# ModuleInter.net
KiCad netlist of a schematic drawn in Altium Designer
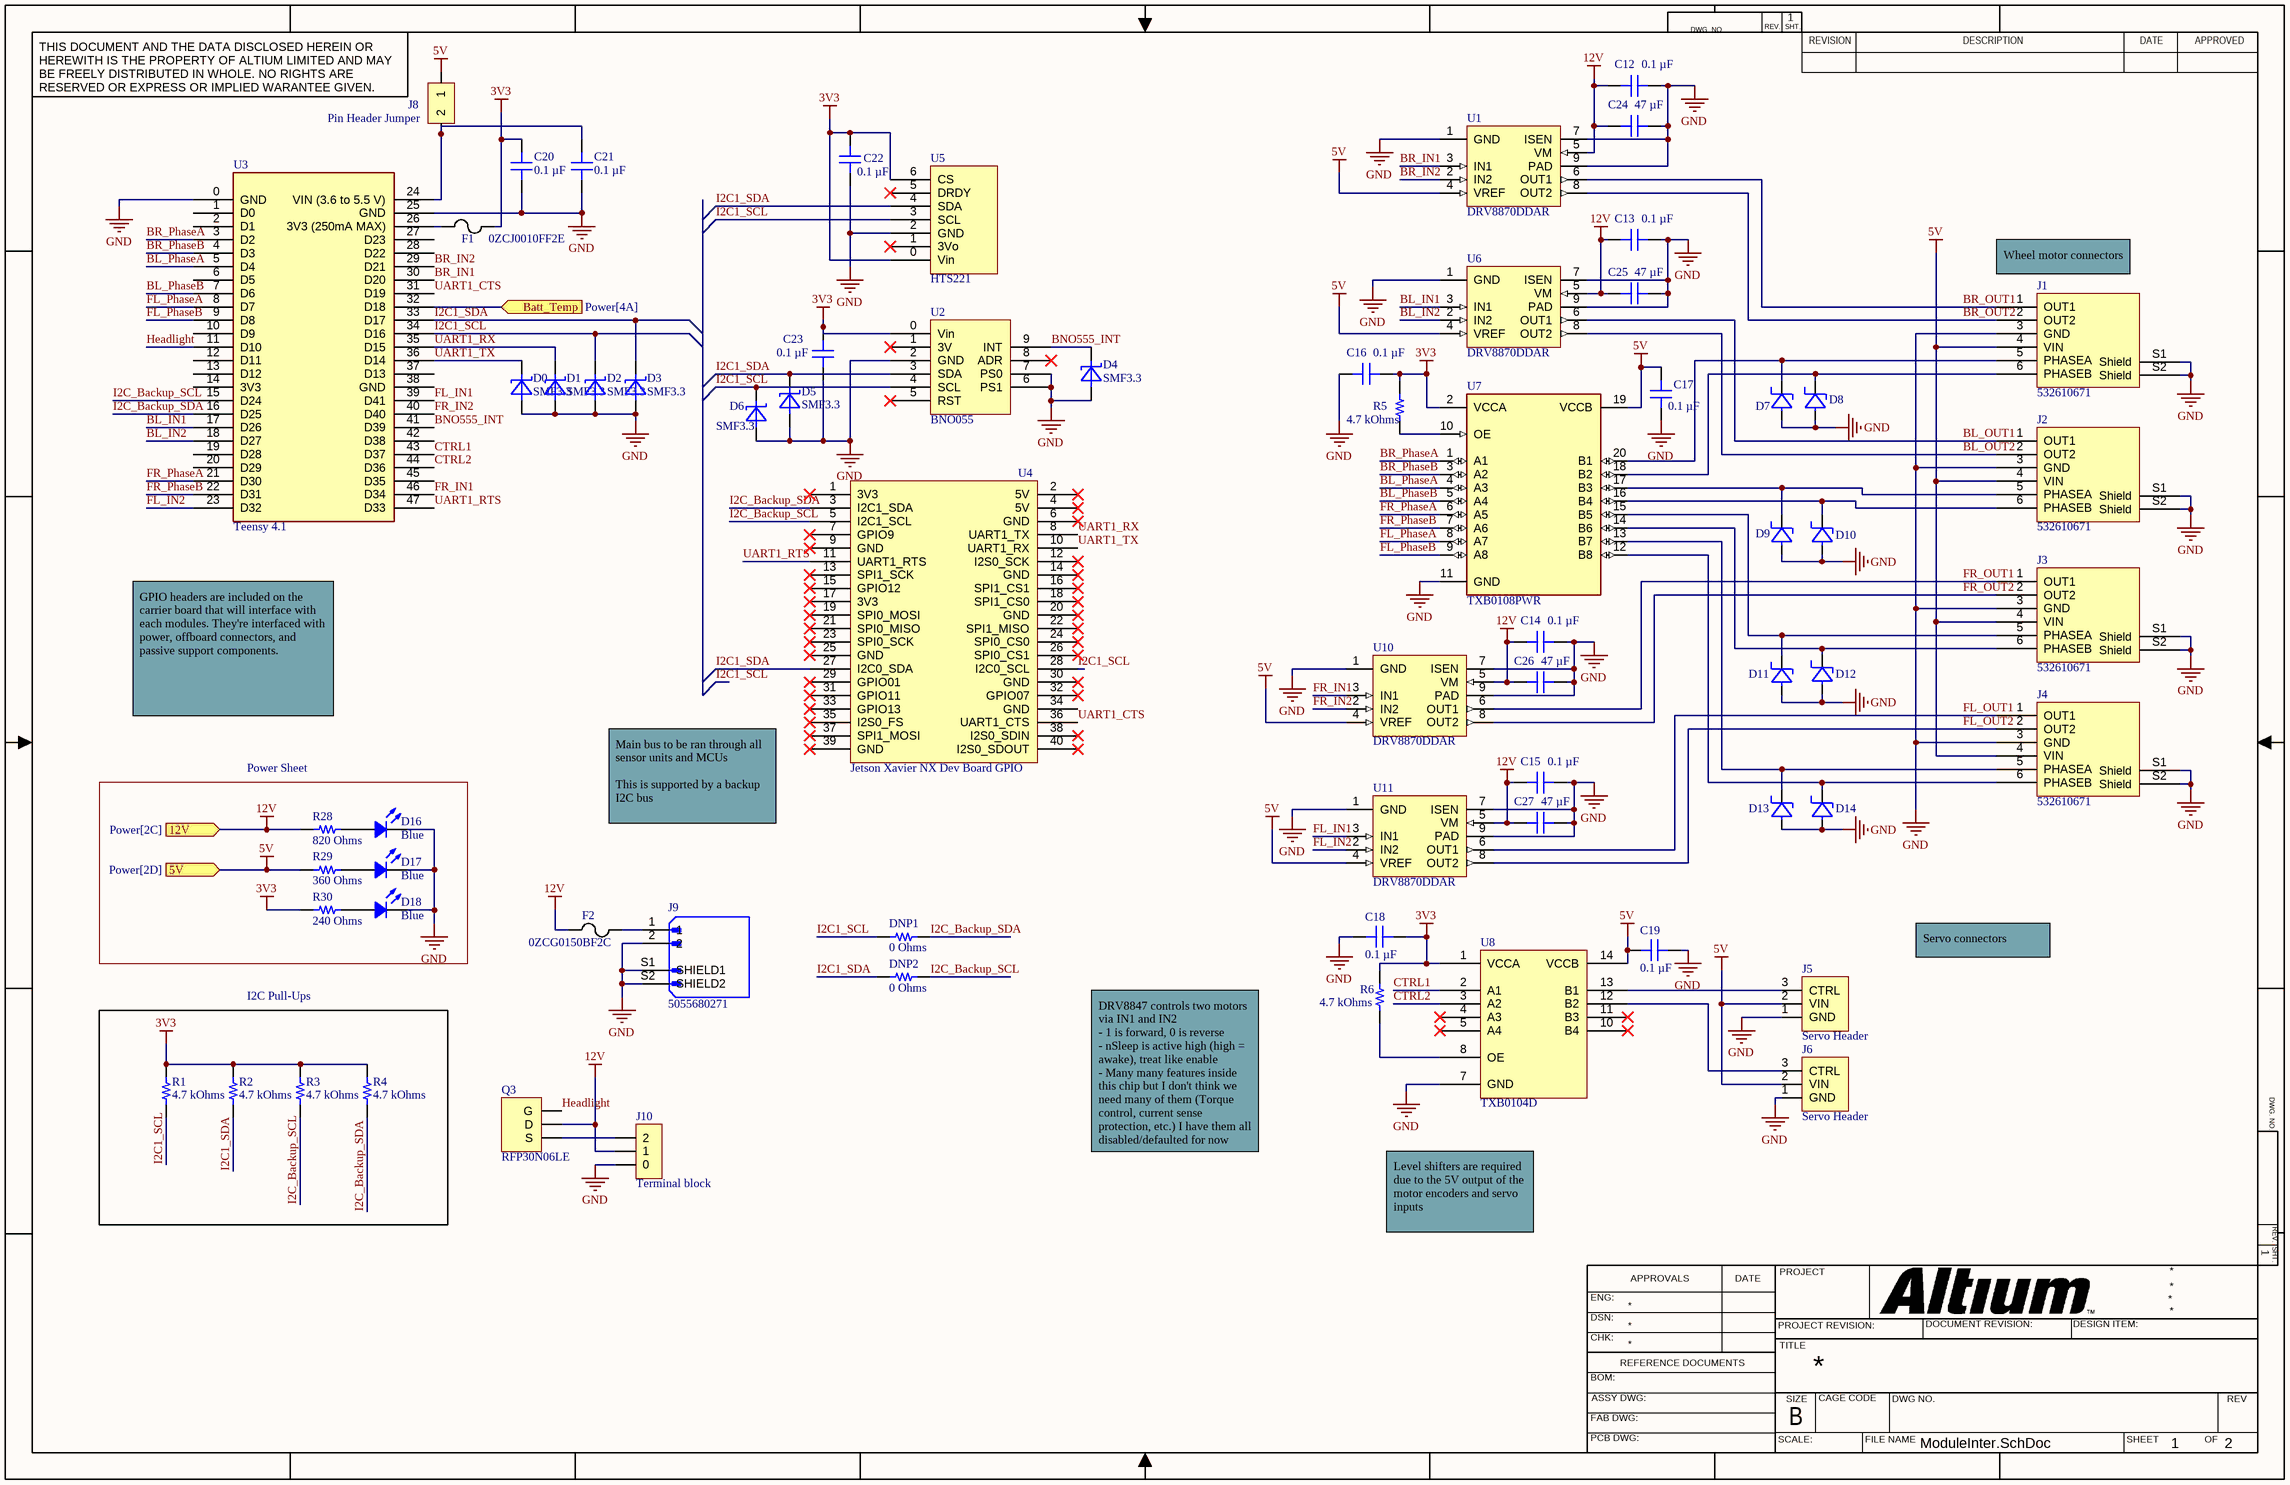
[diagram p0: ModuleInter.SchDoc]

(export (version "E")
  (design (tool "Eeschema 10.0.6"))
  (components
    (comp (ref "C12")
      (value "0.1 µF")
      (footprint "CAP 1206_3216 - 0.8MM")
      (description "CAP CER 0.1UF 50V Y5V 1206")
      (fields (field (name "PART NUMBER") "CC1206MRY5V9BB104") (field (name "MANUFACTURER") "Yageo"))
      (libsource (lib "Celestial Altium Library - altium_library") (part "Capacitor"))
    )
    (comp (ref "C13")
      (value "0.1 µF")
      (footprint "CAP 1206_3216 - 0.8MM")
      (description "CAP CER 0.1UF 50V Y5V 1206")
      (fields (field (name "PART NUMBER") "CC1206MRY5V9BB104") (field (name "MANUFACTURER") "Yageo"))
      (libsource (lib "Celestial Altium Library - altium_library") (part "Capacitor"))
    )
    (comp (ref "C14")
      (value "0.1 µF")
      (footprint "CAP 1206_3216 - 0.8MM")
      (description "CAP CER 0.1UF 50V Y5V 1206")
      (fields (field (name "PART NUMBER") "CC1206MRY5V9BB104") (field (name "MANUFACTURER") "Yageo"))
      (libsource (lib "Celestial Altium Library - altium_library") (part "Capacitor"))
    )
    (comp (ref "C15")
      (value "0.1 µF")
      (footprint "CAP 1206_3216 - 0.8MM")
      (description "CAP CER 0.1UF 50V Y5V 1206")
      (fields (field (name "PART NUMBER") "CC1206MRY5V9BB104") (field (name "MANUFACTURER") "Yageo"))
      (libsource (lib "Celestial Altium Library - altium_library") (part "Capacitor"))
    )
    (comp (ref "C16")
      (value "0.1 µF")
      (footprint "CAP 1206_3216 - 0.8MM")
      (description "CAP CER 0.1UF 50V Y5V 1206")
      (fields (field (name "PART NUMBER") "CC1206MRY5V9BB104") (field (name "MANUFACTURER") "Yageo"))
      (libsource (lib "Celestial Altium Library - altium_library") (part "Capacitor"))
    )
    (comp (ref "C17")
      (value "0.1 µF")
      (footprint "CAP 1206_3216 - 0.8MM")
      (description "CAP CER 0.1UF 50V Y5V 1206")
      (fields (field (name "PART NUMBER") "CC1206MRY5V9BB104") (field (name "MANUFACTURER") "Yageo"))
      (libsource (lib "Celestial Altium Library - altium_library") (part "Capacitor"))
    )
    (comp (ref "C18")
      (value "0.1 µF")
      (footprint "CAP 1206_3216 - 0.8MM")
      (description "CAP CER 0.1UF 50V Y5V 1206")
      (fields (field (name "PART NUMBER") "CC1206MRY5V9BB104") (field (name "MANUFACTURER") "Yageo"))
      (libsource (lib "Celestial Altium Library - altium_library") (part "Capacitor"))
    )
    (comp (ref "C19")
      (value "0.1 µF")
      (footprint "CAP 1206_3216 - 0.8MM")
      (description "CAP CER 0.1UF 50V Y5V 1206")
      (fields (field (name "PART NUMBER") "CC1206MRY5V9BB104") (field (name "MANUFACTURER") "Yageo"))
      (libsource (lib "Celestial Altium Library - altium_library") (part "Capacitor"))
    )
    (comp (ref "C20")
      (value "0.1 µF")
      (footprint "CAP 1206_3216 - 0.8MM")
      (description "CAP CER 0.1UF 50V Y5V 1206")
      (fields (field (name "PART NUMBER") "CC1206MRY5V9BB104") (field (name "MANUFACTURER") "Yageo"))
      (libsource (lib "Celestial Altium Library - altium_library") (part "Capacitor"))
    )
    (comp (ref "C21")
      (value "0.1 µF")
      (footprint "CAP 1206_3216 - 0.8MM")
      (description "CAP CER 0.1UF 50V Y5V 1206")
      (fields (field (name "PART NUMBER") "CC1206MRY5V9BB104") (field (name "MANUFACTURER") "Yageo"))
      (libsource (lib "Celestial Altium Library - altium_library") (part "Capacitor"))
    )
    (comp (ref "C22")
      (value "0.1 µF")
      (footprint "CAP 1206_3216 - 0.8MM")
      (description "CAP CER 0.1UF 50V Y5V 1206")
      (fields (field (name "PART NUMBER") "CC1206MRY5V9BB104") (field (name "MANUFACTURER") "Yageo"))
      (libsource (lib "Celestial Altium Library - altium_library") (part "Capacitor"))
    )
    (comp (ref "C23")
      (value "0.1 µF")
      (footprint "CAP 1206_3216 - 0.8MM")
      (description "CAP CER 0.1UF 50V Y5V 1206")
      (fields (field (name "PART NUMBER") "CC1206MRY5V9BB104") (field (name "MANUFACTURER") "Yageo"))
      (libsource (lib "Celestial Altium Library - altium_library") (part "Capacitor"))
    )
    (comp (ref "C24")
      (value "47 µF")
      (footprint "CAP 1206_3216 - 0.8MM")
      (description "CAP CER 47UF 6.3V X5R 1206")
      (fields (field (name "PART NUMBER") "JMK316ABJ476MD-T") (field (name "MANUFACTURER") "Taiyo Yuden"))
      (libsource (lib "Celestial Altium Library - altium_library") (part "Capacitor"))
    )
    (comp (ref "C25")
      (value "47 µF")
      (footprint "CAP 1206_3216 - 0.8MM")
      (description "CAP CER 47UF 6.3V X5R 1206")
      (fields (field (name "PART NUMBER") "JMK316ABJ476MD-T") (field (name "MANUFACTURER") "Taiyo Yuden"))
      (libsource (lib "Celestial Altium Library - altium_library") (part "Capacitor"))
    )
    (comp (ref "C26")
      (value "47 µF")
      (footprint "CAP 1206_3216 - 0.8MM")
      (description "CAP CER 47UF 6.3V X5R 1206")
      (fields (field (name "PART NUMBER") "JMK316ABJ476MD-T") (field (name "MANUFACTURER") "Taiyo Yuden"))
      (libsource (lib "Celestial Altium Library - altium_library") (part "Capacitor"))
    )
    (comp (ref "C27")
      (value "47 µF")
      (footprint "CAP 1206_3216 - 0.8MM")
      (description "CAP CER 47UF 6.3V X5R 1206")
      (fields (field (name "PART NUMBER") "JMK316ABJ476MD-T") (field (name "MANUFACTURER") "Taiyo Yuden"))
      (libsource (lib "Celestial Altium Library - altium_library") (part "Capacitor"))
    )
    (comp (ref "D0")
      (value "SMF3.3")
      (footprint "SODFL3718X108N")
      (description "6.8V Clamp 30A Ipp Tvs Diode Surface Mount SOD-123FL")
      (fields (field (name "DIGI-KEY_PART_NUMBER") "F7701CT-ND") (field (name "MF") "Littelfuse Inc."))
      (libsource (lib "CBSchLib") (part "SMF3.3"))
    )
    (comp (ref "D1")
      (value "SMF3.3")
      (footprint "SODFL3718X108N")
      (description "6.8V Clamp 30A Ipp Tvs Diode Surface Mount SOD-123FL")
      (fields (field (name "DIGI-KEY_PART_NUMBER") "F7701CT-ND") (field (name "MF") "Littelfuse Inc."))
      (libsource (lib "CBSchLib") (part "SMF3.3"))
    )
    (comp (ref "D2")
      (value "SMF3.3")
      (footprint "SODFL3718X108N")
      (description "6.8V Clamp 30A Ipp Tvs Diode Surface Mount SOD-123FL")
      (fields (field (name "DIGI-KEY_PART_NUMBER") "F7701CT-ND") (field (name "MF") "Littelfuse Inc."))
      (libsource (lib "CBSchLib") (part "SMF3.3"))
    )
    (comp (ref "D3")
      (value "SMF3.3")
      (footprint "SODFL3718X108N")
      (description "6.8V Clamp 30A Ipp Tvs Diode Surface Mount SOD-123FL")
      (fields (field (name "DIGI-KEY_PART_NUMBER") "F7701CT-ND") (field (name "MF") "Littelfuse Inc."))
      (libsource (lib "CBSchLib") (part "SMF3.3"))
    )
    (comp (ref "D4")
      (value "SMF3.3")
      (footprint "SODFL3718X108N")
      (description "6.8V Clamp 30A Ipp Tvs Diode Surface Mount SOD-123FL")
      (fields (field (name "DIGI-KEY_PART_NUMBER") "F7701CT-ND") (field (name "MF") "Littelfuse Inc."))
      (libsource (lib "CBSchLib") (part "SMF3.3"))
    )
    (comp (ref "D5")
      (value "SMF3.3")
      (footprint "SODFL3718X108N")
      (description "6.8V Clamp 30A Ipp Tvs Diode Surface Mount SOD-123FL")
      (fields (field (name "DIGI-KEY_PART_NUMBER") "F7701CT-ND") (field (name "MF") "Littelfuse Inc."))
      (libsource (lib "CBSchLib") (part "SMF3.3"))
    )
    (comp (ref "D6")
      (value "SMF3.3")
      (footprint "SODFL3718X108N")
      (description "6.8V Clamp 30A Ipp Tvs Diode Surface Mount SOD-123FL")
      (fields (field (name "DIGI-KEY_PART_NUMBER") "F7701CT-ND") (field (name "MF") "Littelfuse Inc."))
      (libsource (lib "CBSchLib") (part "SMF3.3"))
    )
    (comp (ref "D7")
      (value "SMBJ5.0CA-13-F")
      (footprint "SMB_DIO")
      (description "DIODE ZENER 6.2V 600W")
      (libsource (lib "CBSchLib") (part "SMBJ5.0CA-13-F"))
    )
    (comp (ref "D8")
      (value "SMBJ5.0CA-13-F")
      (footprint "SMB_DIO")
      (description "DIODE ZENER 6.2V 600W")
      (libsource (lib "CBSchLib") (part "SMBJ5.0CA-13-F"))
    )
    (comp (ref "D9")
      (value "SMBJ5.0CA-13-F")
      (footprint "SMB_DIO")
      (description "DIODE ZENER 6.2V 600W")
      (libsource (lib "CBSchLib") (part "SMBJ5.0CA-13-F"))
    )
    (comp (ref "D10")
      (value "SMBJ5.0CA-13-F")
      (footprint "SMB_DIO")
      (description "DIODE ZENER 6.2V 600W")
      (libsource (lib "CBSchLib") (part "SMBJ5.0CA-13-F"))
    )
    (comp (ref "D11")
      (value "SMBJ5.0CA-13-F")
      (footprint "SMB_DIO")
      (description "DIODE ZENER 6.2V 600W")
      (libsource (lib "CBSchLib") (part "SMBJ5.0CA-13-F"))
    )
    (comp (ref "D12")
      (value "SMBJ5.0CA-13-F")
      (footprint "SMB_DIO")
      (description "DIODE ZENER 6.2V 600W")
      (libsource (lib "CBSchLib") (part "SMBJ5.0CA-13-F"))
    )
    (comp (ref "D13")
      (value "SMBJ5.0CA-13-F")
      (footprint "SMB_DIO")
      (description "DIODE ZENER 6.2V 600W")
      (libsource (lib "CBSchLib") (part "SMBJ5.0CA-13-F"))
    )
    (comp (ref "D14")
      (value "SMBJ5.0CA-13-F")
      (footprint "SMB_DIO")
      (description "DIODE ZENER 6.2V 600W")
      (libsource (lib "CBSchLib") (part "SMBJ5.0CA-13-F"))
    )
    (comp (ref "D16")
      (value "Blue")
      (footprint "LED 1206_3216 BLUE")
      (description "LED BLUE CLEAR 1206 SMD")
      (fields (field (name "PART NUMBER") "LTST-C150TBKT") (field (name "MANUFACTURER") "Lite-On Inc."))
      (libsource (lib "Celestial Altium Library - altium_library") (part "LED"))
    )
    (comp (ref "D17")
      (value "Blue")
      (footprint "LED 1206_3216 BLUE")
      (description "LED BLUE CLEAR 1206 SMD")
      (fields (field (name "PART NUMBER") "LTST-C150TBKT") (field (name "MANUFACTURER") "Lite-On Inc."))
      (libsource (lib "Celestial Altium Library - altium_library") (part "LED"))
    )
    (comp (ref "D18")
      (value "Blue")
      (footprint "LED 1206_3216 BLUE")
      (description "LED BLUE CLEAR 1206 SMD")
      (fields (field (name "PART NUMBER") "LTST-C150TBKT") (field (name "MANUFACTURER") "Lite-On Inc."))
      (libsource (lib "Celestial Altium Library - altium_library") (part "LED"))
    )
    (comp (ref "DNP1")
      (value "0 Ohms")
      (footprint "RES 1206_3216")
      (description "RES 0 OHM JUMPER 1/2W 1206")
      (fields (field (name "PART NUMBER") "RC1206JR-7W0RL") (field (name "MANUFACTURER") "Yageo"))
      (libsource (lib "Celestial Altium Library - altium_library") (part "Resistor"))
    )
    (comp (ref "DNP2")
      (value "0 Ohms")
      (footprint "RES 1206_3216")
      (description "RES 0 OHM JUMPER 1/2W 1206")
      (fields (field (name "PART NUMBER") "RC1206JR-7W0RL") (field (name "MANUFACTURER") "Yageo"))
      (libsource (lib "Celestial Altium Library - altium_library") (part "Resistor"))
    )
    (comp (ref "F1")
      (value "0ZCJ0010FF2E")
      (footprint "RESC3216X125N")
      (description "Polymeric PTC Resettable Fuse 60V 100 mA Ih Surface Mount 1206 (3216 Metric), Concave")
      (fields (field (name "MF") "Bel Fuse"))
      (libsource (lib "CBSchLib") (part "0ZCJ0010FF2E"))
    )
    (comp (ref "F2")
      (value "0ZCG0150BF2C")
      (footprint "0ZCG_BEL")
      (description "Polymeric PTC Resettable Fuse 24V 1.5 A Ih Surface Mount 1812 (4532 Metric), Concave")
      (fields (field (name "COPYRIGHT") "Copyright (C) 2023 Ultra Librarian. All rights reserved."))
      (libsource (lib "CBSchLib") (part "0ZCG0150BF2C"))
    )
    (comp (ref "J1")
      (value "532610671")
      (footprint "MOLEX_532610671")
      (description "Conn Shrouded Header (4 Sides) HDR 6 POS 1.25mm Solder RA Side Entry SMD PicoBlade™ T/R")
      (libsource (lib "CBSchLib") (part "532610671"))
    )
    (comp (ref "J2")
      (value "532610671")
      (footprint "MOLEX_532610671")
      (description "Conn Shrouded Header (4 Sides) HDR 6 POS 1.25mm Solder RA Side Entry SMD PicoBlade™ T/R")
      (libsource (lib "CBSchLib") (part "532610671"))
    )
    (comp (ref "J3")
      (value "532610671")
      (footprint "MOLEX_532610671")
      (description "Conn Shrouded Header (4 Sides) HDR 6 POS 1.25mm Solder RA Side Entry SMD PicoBlade™ T/R")
      (libsource (lib "CBSchLib") (part "532610671"))
    )
    (comp (ref "J4")
      (value "532610671")
      (footprint "MOLEX_532610671")
      (description "Conn Shrouded Header (4 Sides) HDR 6 POS 1.25mm Solder RA Side Entry SMD PicoBlade™ T/R")
      (libsource (lib "CBSchLib") (part "532610671"))
    )
    (comp (ref "J5")
      (value "Servo Header")
      (footprint "Servo Header")
      (description "3P jumper header")
      (libsource (lib "CBSchLib") (part "Servo Header"))
    )
    (comp (ref "J6")
      (value "Servo Header")
      (footprint "Servo Header")
      (description "3P jumper header")
      (libsource (lib "CBSchLib") (part "Servo Header"))
    )
    (comp (ref "J8")
      (value "Pin Header Jumper")
      (footprint "Pin Header Jumper")
      (libsource (lib "CBSchLib") (part "Pin Header Jumper"))
    )
    (comp (ref "J9")
      (value "5055680271")
      (footprint "MOLEX_5055680271")
      (fields (field (name "MF") "Molex"))
      (libsource (lib "CBSchLib") (part "5055680271"))
    )
    (comp (ref "J10")
      (value "Terminal block")
      (footprint "Terminal Holes")
      (libsource (lib "CBSchLib") (part "Terminal block"))
    )
    (comp (ref "Q3")
      (value "RFP30N06LE")
      (footprint "PWM Fet")
      (description "Standin fro PWM mosfet for Light bar")
      (libsource (lib "CBSchLib") (part "RFP30N06LE"))
    )
    (comp (ref "R1")
      (value "4.7 kOhms")
      (footprint "RES 1206_3216")
      (description "RES SMD 4.7K OHM 1% 1/4W 1206")
      (fields
        (field (name "PART NUMBER") "CRG1206F4K7")
        (field (name "MANUFACTURER") "TE Connectivity Passive Product")
      )
      (libsource (lib "Celestial Altium Library - altium_library") (part "Resistor"))
    )
    (comp (ref "R2")
      (value "4.7 kOhms")
      (footprint "RES 1206_3216")
      (description "RES SMD 4.7K OHM 1% 1/4W 1206")
      (fields
        (field (name "PART NUMBER") "CRG1206F4K7")
        (field (name "MANUFACTURER") "TE Connectivity Passive Product")
      )
      (libsource (lib "Celestial Altium Library - altium_library") (part "Resistor"))
    )
    (comp (ref "R3")
      (value "4.7 kOhms")
      (footprint "RES 1206_3216")
      (description "RES SMD 4.7K OHM 1% 1/4W 1206")
      (fields
        (field (name "PART NUMBER") "CRG1206F4K7")
        (field (name "MANUFACTURER") "TE Connectivity Passive Product")
      )
      (libsource (lib "Celestial Altium Library - altium_library") (part "Resistor"))
    )
    (comp (ref "R4")
      (value "4.7 kOhms")
      (footprint "RES 1206_3216")
      (description "RES SMD 4.7K OHM 1% 1/4W 1206")
      (fields
        (field (name "PART NUMBER") "CRG1206F4K7")
        (field (name "MANUFACTURER") "TE Connectivity Passive Product")
      )
      (libsource (lib "Celestial Altium Library - altium_library") (part "Resistor"))
    )
    (comp (ref "R5")
      (value "4.7 kOhms")
      (footprint "RES 1206_3216")
      (description "RES SMD 4.7K OHM 1% 1/4W 1206")
      (fields
        (field (name "PART NUMBER") "CRG1206F4K7")
        (field (name "MANUFACTURER") "TE Connectivity Passive Product")
      )
      (libsource (lib "Celestial Altium Library - altium_library") (part "Resistor"))
    )
    (comp (ref "R6")
      (value "4.7 kOhms")
      (footprint "RES 1206_3216")
      (description "RES SMD 4.7K OHM 1% 1/4W 1206")
      (fields
        (field (name "PART NUMBER") "CRG1206F4K7")
        (field (name "MANUFACTURER") "TE Connectivity Passive Product")
      )
      (libsource (lib "Celestial Altium Library - altium_library") (part "Resistor"))
    )
    (comp (ref "R28")
      (value "820 Ohms")
      (footprint "RES 1206_3216")
      (description "RES 820 OHM 1% 1/4W 1206")
      (fields
        (field (name "PART NUMBER") "CRGCQ1206F820R")
        (field (name "MANUFACTURER") "TE Connectivity Passive Product")
      )
      (libsource (lib "Celestial Altium Library - altium_library") (part "Resistor"))
    )
    (comp (ref "R29")
      (value "360 Ohms")
      (footprint "RES 1206_3216")
      (description "RES 360 OHM 1% 1/4W 1206")
      (fields
        (field (name "PART NUMBER") "RMCF1206FT360R")
        (field (name "MANUFACTURER") "Stackpole Electronics Inc")
      )
      (libsource (lib "Celestial Altium Library - altium_library") (part "Resistor"))
    )
    (comp (ref "R30")
      (value "240 Ohms")
      (footprint "RES 1206_3216")
      (description "RCS1206 100 240R 1% ET1 E3")
      (fields (field (name "PART NUMBER") "RCS1206240RFKEA") (field (name "MANUFACTURER") "Vishay Dale"))
      (libsource (lib "Celestial Altium Library - altium_library") (part "Resistor"))
    )
    (comp (ref "U1")
      (value "DRV8870DDAR")
      (footprint "VREG_LM5017MR/NOPB")
      (description "45-V, 3.6-A H-bridge motor driver with current regulation 8-SO PowerPAD -40 to 125")
      (fields (field (name "DIGI-KEY_PART_NUMBER") "296-42660-1-ND") (field (name "MF") "Texas Instruments"))
      (libsource (lib "CBSchLib") (part "DRV8870DDAR"))
    )
    (comp (ref "U2")
      (value "BNO055")
      (footprint "BNO555 - Header Mode")
      (libsource (lib "CBSchLib") (part "BNO055"))
    )
    (comp (ref "U3")
      (value "Teensy 4.1")
      (footprint "Teensy 4.1")
      (libsource (lib "CBSchLib") (part "Teensy 4.1"))
    )
    (comp (ref "U4")
      (value "Jetson Xavier NX Dev Board GPIO")
      (footprint "Xavier Interface")
      (libsource (lib "CBSchLib") (part "Jetson Xavier NX Dev Board GPIO"))
    )
    (comp (ref "U5") (value "HTS221") (footprint "HTS221") (libsource (lib "CBSchLib") (part "HTS221")))
    (comp (ref "U6")
      (value "DRV8870DDAR")
      (footprint "VREG_LM5017MR/NOPB")
      (description "45-V, 3.6-A H-bridge motor driver with current regulation 8-SO PowerPAD -40 to 125")
      (fields (field (name "DIGI-KEY_PART_NUMBER") "296-42660-1-ND") (field (name "MF") "Texas Instruments"))
      (libsource (lib "CBSchLib") (part "DRV8870DDAR"))
    )
    (comp (ref "U7")
      (value "TXB0108PWR")
      (footprint "SOP65P640X120-20N")
      (description "8-Bit Bidirectional Voltage-Level Shifter with Auto Direction Sensing and +/-15-kV ESD Protect")
      (fields (field (name "MF") "Texas Instruments") (field (name "DIGI-KEY_PART_NUMBER") "296-21527-2-ND"))
      (libsource (lib "CBSchLib") (part "TXB0108PWR"))
    )
    (comp (ref "U8")
      (value "TXB0104D")
      (footprint "TI SOIC-14 D")
      (description "IC TRNSLTR BIDIRECTIONAL 14SOIC")
      (fields (field (name "MANUFACTURER") "Texas Instruments"))
      (libsource (lib "Celestial Altium Library - altium_library") (part "TI TXB0104"))
    )
    (comp (ref "U10")
      (value "DRV8870DDAR")
      (footprint "VREG_LM5017MR/NOPB")
      (description "45-V, 3.6-A H-bridge motor driver with current regulation 8-SO PowerPAD -40 to 125")
      (fields (field (name "DIGI-KEY_PART_NUMBER") "296-42660-1-ND") (field (name "MF") "Texas Instruments"))
      (libsource (lib "CBSchLib") (part "DRV8870DDAR"))
    )
    (comp (ref "U11")
      (value "DRV8870DDAR")
      (footprint "VREG_LM5017MR/NOPB")
      (description "45-V, 3.6-A H-bridge motor driver with current regulation 8-SO PowerPAD -40 to 125")
      (fields (field (name "DIGI-KEY_PART_NUMBER") "296-42660-1-ND") (field (name "MF") "Texas Instruments"))
      (libsource (lib "CBSchLib") (part "DRV8870DDAR"))
    )
  )
  (nets
    (net (code "1") (name "/BL_IN1") (class "Default")
      (node (ref "U3") (pin "17") (pinfunction "D26_17") (pintype "passive"))
      (node (ref "U6") (pin "3") (pinfunction "IN1_3") (pintype "input"))
    )
    (net (code "2") (name "/BL_IN2") (class "Default")
      (node (ref "U3") (pin "18") (pinfunction "D27_18") (pintype "passive"))
      (node (ref "U6") (pin "2") (pinfunction "IN2_2") (pintype "input"))
    )
    (net (code "3") (name "/BL_OUT1") (class "Default")
      (node (ref "J2") (pin "1") (pinfunction "OUT1_1") (pintype "passive"))
      (node (ref "U6") (pin "6") (pinfunction "OUT1_6") (pintype "output"))
    )
    (net (code "4") (name "/BL_OUT2") (class "Default")
      (node (ref "J2") (pin "2") (pinfunction "OUT2_2") (pintype "passive"))
      (node (ref "U6") (pin "8") (pinfunction "OUT2_8") (pintype "output"))
    )
    (net (code "5") (name "/BL_PhaseA") (class "Default")
      (node (ref "U3") (pin "5") (pinfunction "D4_5") (pintype "passive"))
      (node (ref "U7") (pin "4") (pinfunction "A3_4") (pintype "bidirectional"))
    )
    (net (code "6") (name "/BL_PhaseB") (class "Default")
      (node (ref "U3") (pin "7") (pinfunction "D6_7") (pintype "passive"))
      (node (ref "U7") (pin "5") (pinfunction "A4_5") (pintype "bidirectional"))
    )
    (net (code "7") (name "/BNO555_INT") (class "Default")
      (node (ref "D4") (pin "A") (pinfunction "C_A") (pintype "passive"))
      (node (ref "U2") (pin "9") (pinfunction "INT_9") (pintype "passive"))
      (node (ref "U3") (pin "41") (pinfunction "D39_41") (pintype "passive"))
    )
    (net (code "8") (name "/BR_IN1") (class "Default")
      (node (ref "U1") (pin "3") (pinfunction "IN1_3") (pintype "input"))
      (node (ref "U3") (pin "30") (pinfunction "D20_30") (pintype "passive"))
    )
    (net (code "9") (name "/BR_IN2") (class "Default")
      (node (ref "U1") (pin "2") (pinfunction "IN2_2") (pintype "input"))
      (node (ref "U3") (pin "29") (pinfunction "D21_29") (pintype "passive"))
    )
    (net (code "10") (name "/BR_OUT1") (class "Default")
      (node (ref "J1") (pin "1") (pinfunction "OUT1_1") (pintype "passive"))
      (node (ref "U1") (pin "6") (pinfunction "OUT1_6") (pintype "output"))
    )
    (net (code "11") (name "/BR_OUT2") (class "Default")
      (node (ref "J1") (pin "2") (pinfunction "OUT2_2") (pintype "passive"))
      (node (ref "U1") (pin "8") (pinfunction "OUT2_8") (pintype "output"))
    )
    (net (code "12") (name "/BR_PhaseA") (class "Default")
      (node (ref "U3") (pin "3") (pinfunction "D2_3") (pintype "passive"))
      (node (ref "U7") (pin "1") (pinfunction "A1_1") (pintype "bidirectional"))
    )
    (net (code "13") (name "/BR_PhaseB") (class "Default")
      (node (ref "U3") (pin "4") (pinfunction "D3_4") (pintype "passive"))
      (node (ref "U7") (pin "3") (pinfunction "A2_3") (pintype "bidirectional"))
    )
    (net (code "14") (name "/Batt_Temp") (class "Default")
      (node (ref "U3") (pin "32") (pinfunction "D18_32") (pintype "passive"))
    )
    (net (code "15") (name "/CTRL1") (class "Default")
      (node (ref "U3") (pin "43") (pinfunction "D37_43") (pintype "passive"))
      (node (ref "U8") (pin "2") (pinfunction "A1_2") (pintype "passive"))
    )
    (net (code "16") (name "/CTRL2") (class "Default")
      (node (ref "U3") (pin "44") (pinfunction "D36_44") (pintype "passive"))
      (node (ref "U8") (pin "3") (pinfunction "A2_3") (pintype "passive"))
    )
    (net (code "17") (name "/FL_IN1") (class "Default")
      (node (ref "U11") (pin "3") (pinfunction "IN1_3") (pintype "input"))
      (node (ref "U3") (pin "39") (pinfunction "D41_39") (pintype "passive"))
    )
    (net (code "18") (name "/FL_IN2") (class "Default")
      (node (ref "U11") (pin "2") (pinfunction "IN2_2") (pintype "input"))
      (node (ref "U3") (pin "23") (pinfunction "D32_23") (pintype "passive"))
    )
    (net (code "19") (name "/FL_OUT1") (class "Default")
      (node (ref "J4") (pin "1") (pinfunction "OUT1_1") (pintype "passive"))
      (node (ref "U11") (pin "6") (pinfunction "OUT1_6") (pintype "output"))
    )
    (net (code "20") (name "/FL_OUT2") (class "Default")
      (node (ref "J4") (pin "2") (pinfunction "OUT2_2") (pintype "passive"))
      (node (ref "U11") (pin "8") (pinfunction "OUT2_8") (pintype "output"))
    )
    (net (code "21") (name "/FL_PhaseA") (class "Default")
      (node (ref "U3") (pin "8") (pinfunction "D7_8") (pintype "passive"))
      (node (ref "U7") (pin "8") (pinfunction "A7_8") (pintype "bidirectional"))
    )
    (net (code "22") (name "/FL_PhaseB") (class "Default")
      (node (ref "U3") (pin "9") (pinfunction "D8_9") (pintype "passive"))
      (node (ref "U7") (pin "9") (pinfunction "A8_9") (pintype "bidirectional"))
    )
    (net (code "23") (name "/FR_IN1") (class "Default")
      (node (ref "U10") (pin "3") (pinfunction "IN1_3") (pintype "input"))
      (node (ref "U3") (pin "46") (pinfunction "D34_46") (pintype "passive"))
    )
    (net (code "24") (name "/FR_IN2") (class "Default")
      (node (ref "U10") (pin "2") (pinfunction "IN2_2") (pintype "input"))
      (node (ref "U3") (pin "40") (pinfunction "D40_40") (pintype "passive"))
    )
    (net (code "25") (name "/FR_OUT1") (class "Default")
      (node (ref "J3") (pin "1") (pinfunction "OUT1_1") (pintype "passive"))
      (node (ref "U10") (pin "6") (pinfunction "OUT1_6") (pintype "output"))
    )
    (net (code "26") (name "/FR_OUT2") (class "Default")
      (node (ref "J3") (pin "2") (pinfunction "OUT2_2") (pintype "passive"))
      (node (ref "U10") (pin "8") (pinfunction "OUT2_8") (pintype "output"))
    )
    (net (code "27") (name "/FR_PhaseA") (class "Default")
      (node (ref "U3") (pin "21") (pinfunction "D30_21") (pintype "passive"))
      (node (ref "U7") (pin "6") (pinfunction "A5_6") (pintype "bidirectional"))
    )
    (net (code "28") (name "/FR_PhaseB") (class "Default")
      (node (ref "U3") (pin "22") (pinfunction "D31_22") (pintype "passive"))
      (node (ref "U7") (pin "7") (pinfunction "A6_7") (pintype "bidirectional"))
    )
    (net (code "29") (name "/Headlight") (class "Default")
      (node (ref "Q3") (pin "0") (pinfunction "G_0") (pintype "passive"))
      (node (ref "U3") (pin "11") (pinfunction "D10_11") (pintype "passive"))
    )
    (net (code "30") (name "/I2C1_SCL") (class "Default")
      (node (ref "D2") (pin "A") (pinfunction "C_A") (pintype "passive"))
      (node (ref "D6") (pin "A") (pinfunction "C_A") (pintype "passive"))
      (node (ref "DNP1") (pin "1") (pinfunction "1_1") (pintype "passive"))
      (node (ref "R1") (pin "1") (pinfunction "1_1") (pintype "passive"))
      (node (ref "U2") (pin "4") (pinfunction "SCL_4") (pintype "passive"))
      (node (ref "U3") (pin "34") (pinfunction "D16_34") (pintype "passive"))
      (node (ref "U4") (pin "28") (pinfunction "I2C0_SCL_28") (pintype "passive"))
      (node (ref "U5") (pin "3") (pinfunction "SCL_3") (pintype "passive"))
    )
    (net (code "31") (name "/I2C1_SDA") (class "Default")
      (node (ref "D3") (pin "A") (pinfunction "C_A") (pintype "passive"))
      (node (ref "D5") (pin "A") (pinfunction "C_A") (pintype "passive"))
      (node (ref "DNP2") (pin "1") (pinfunction "1_1") (pintype "passive"))
      (node (ref "R2") (pin "1") (pinfunction "1_1") (pintype "passive"))
      (node (ref "U2") (pin "3") (pinfunction "SDA_3") (pintype "passive"))
      (node (ref "U3") (pin "33") (pinfunction "D17_33") (pintype "passive"))
      (node (ref "U4") (pin "27") (pinfunction "I2C0_SDA_27") (pintype "passive"))
      (node (ref "U5") (pin "4") (pinfunction "SDA_4") (pintype "passive"))
    )
    (net (code "32") (name "/I2C_Backup_SCL") (class "Default")
      (node (ref "DNP2") (pin "2") (pinfunction "2_2") (pintype "passive"))
      (node (ref "R3") (pin "1") (pinfunction "1_1") (pintype "passive"))
      (node (ref "U3") (pin "15") (pinfunction "D24_15") (pintype "passive"))
      (node (ref "U4") (pin "5") (pinfunction "I2C1_SCL_5") (pintype "passive"))
    )
    (net (code "33") (name "/I2C_Backup_SDA") (class "Default")
      (node (ref "DNP1") (pin "2") (pinfunction "2_2") (pintype "passive"))
      (node (ref "R4") (pin "1") (pinfunction "1_1") (pintype "passive"))
      (node (ref "U3") (pin "16") (pinfunction "D25_16") (pintype "passive"))
      (node (ref "U4") (pin "3") (pinfunction "I2C1_SDA_3") (pintype "passive"))
    )
    (net (code "34") (name "/UART1_CTS") (class "Default")
      (node (ref "U3") (pin "31") (pinfunction "D19_31") (pintype "passive"))
      (node (ref "U4") (pin "36") (pinfunction "UART1_CTS_36") (pintype "passive"))
    )
    (net (code "35") (name "/UART1_RTS") (class "Default")
      (node (ref "U3") (pin "47") (pinfunction "D33_47") (pintype "passive"))
      (node (ref "U4") (pin "11") (pinfunction "UART1_RTS_11") (pintype "passive"))
    )
    (net (code "36") (name "/UART1_RX") (class "Default")
      (node (ref "D1") (pin "A") (pinfunction "C_A") (pintype "passive"))
      (node (ref "U3") (pin "35") (pinfunction "D15_35") (pintype "passive"))
      (node (ref "U4") (pin "8") (pinfunction "UART1_TX_8") (pintype "passive"))
    )
    (net (code "37") (name "/UART1_TX") (class "Default")
      (node (ref "D0") (pin "A") (pinfunction "C_A") (pintype "passive"))
      (node (ref "U3") (pin "36") (pinfunction "D14_36") (pintype "passive"))
      (node (ref "U4") (pin "10") (pinfunction "UART1_RX_10") (pintype "passive"))
    )
    (net (code "38") (name "3V3") (class "Default")
      (node (ref "C16") (pin "1") (pinfunction "1_1") (pintype "passive"))
      (node (ref "C18") (pin "1") (pinfunction "1_1") (pintype "passive"))
      (node (ref "C20") (pin "1") (pinfunction "1_1") (pintype "passive"))
      (node (ref "C22") (pin "1") (pinfunction "1_1") (pintype "passive"))
      (node (ref "C23") (pin "1") (pinfunction "1_1") (pintype "passive"))
      (node (ref "F1") (pin "2") (pinfunction "2_2") (pintype "passive"))
      (node (ref "R1") (pin "2") (pinfunction "2_2") (pintype "passive"))
      (node (ref "R2") (pin "2") (pinfunction "2_2") (pintype "passive"))
      (node (ref "R3") (pin "2") (pinfunction "2_2") (pintype "passive"))
      (node (ref "R30") (pin "1") (pinfunction "1_1") (pintype "passive"))
      (node (ref "R4") (pin "2") (pinfunction "2_2") (pintype "passive"))
      (node (ref "R5") (pin "1") (pinfunction "1_1") (pintype "passive"))
      (node (ref "R6") (pin "2") (pinfunction "2_2") (pintype "passive"))
      (node (ref "U2") (pin "0") (pinfunction "Vin_0") (pintype "passive"))
      (node (ref "U5") (pin "0") (pinfunction "Vin_0") (pintype "passive"))
      (node (ref "U5") (pin "6") (pinfunction "CS_6") (pintype "passive"))
      (node (ref "U7") (pin "2") (pinfunction "VCCA_2") (pintype "power_in"))
      (node (ref "U8") (pin "1") (pinfunction "VCCA_1") (pintype "passive"))
    )
    (net (code "39") (name "5V") (class "Default")
      (node (ref "C17") (pin "1") (pinfunction "1_1") (pintype "passive"))
      (node (ref "C19") (pin "1") (pinfunction "1_1") (pintype "passive"))
      (node (ref "J1") (pin "4") (pinfunction "VIN_4") (pintype "passive"))
      (node (ref "J2") (pin "4") (pinfunction "VIN_4") (pintype "passive"))
      (node (ref "J3") (pin "4") (pinfunction "VIN_4") (pintype "passive"))
      (node (ref "J4") (pin "4") (pinfunction "VIN_4") (pintype "passive"))
      (node (ref "J5") (pin "2") (pinfunction "VIN_2") (pintype "passive"))
      (node (ref "J6") (pin "2") (pinfunction "VIN_2") (pintype "passive"))
      (node (ref "J8") (pin "1") (pinfunction "1_1") (pintype "passive"))
      (node (ref "R29") (pin "1") (pinfunction "1_1") (pintype "passive"))
      (node (ref "U1") (pin "4") (pinfunction "VREF_4") (pintype "input"))
      (node (ref "U10") (pin "4") (pinfunction "VREF_4") (pintype "input"))
      (node (ref "U11") (pin "4") (pinfunction "VREF_4") (pintype "input"))
      (node (ref "U6") (pin "4") (pinfunction "VREF_4") (pintype "input"))
      (node (ref "U7") (pin "19") (pinfunction "VCCB_19") (pintype "power_in"))
      (node (ref "U8") (pin "14") (pinfunction "VCCB_14") (pintype "passive"))
    )
    (net (code "40") (name "12V") (class "Default")
      (node (ref "C12") (pin "2") (pinfunction "2_2") (pintype "passive"))
      (node (ref "C13") (pin "2") (pinfunction "2_2") (pintype "passive"))
      (node (ref "C14") (pin "2") (pinfunction "2_2") (pintype "passive"))
      (node (ref "C15") (pin "2") (pinfunction "2_2") (pintype "passive"))
      (node (ref "C24") (pin "1") (pinfunction "1_1") (pintype "passive"))
      (node (ref "C25") (pin "1") (pinfunction "1_1") (pintype "passive"))
      (node (ref "C26") (pin "1") (pinfunction "1_1") (pintype "passive"))
      (node (ref "C27") (pin "1") (pinfunction "1_1") (pintype "passive"))
      (node (ref "F2") (pin "1") (pinfunction "1_1") (pintype "passive"))
      (node (ref "J10") (pin "1") (pinfunction "1_1") (pintype "passive"))
      (node (ref "Q3") (pin "1") (pinfunction "D_1") (pintype "passive"))
      (node (ref "R28") (pin "1") (pinfunction "1_1") (pintype "passive"))
      (node (ref "U1") (pin "5") (pinfunction "VM_5") (pintype "input"))
      (node (ref "U10") (pin "5") (pinfunction "VM_5") (pintype "input"))
      (node (ref "U11") (pin "5") (pinfunction "VM_5") (pintype "input"))
      (node (ref "U6") (pin "5") (pinfunction "VM_5") (pintype "input"))
    )
    (net (code "41") (name "GND") (class "Default")
      (node (ref "C12") (pin "1") (pinfunction "1_1") (pintype "passive"))
      (node (ref "C13") (pin "1") (pinfunction "1_1") (pintype "passive"))
      (node (ref "C14") (pin "1") (pinfunction "1_1") (pintype "passive"))
      (node (ref "C15") (pin "1") (pinfunction "1_1") (pintype "passive"))
      (node (ref "C16") (pin "2") (pinfunction "2_2") (pintype "passive"))
      (node (ref "C17") (pin "2") (pinfunction "2_2") (pintype "passive"))
      (node (ref "C18") (pin "2") (pinfunction "2_2") (pintype "passive"))
      (node (ref "C19") (pin "2") (pinfunction "2_2") (pintype "passive"))
      (node (ref "C20") (pin "2") (pinfunction "2_2") (pintype "passive"))
      (node (ref "C21") (pin "2") (pinfunction "2_2") (pintype "passive"))
      (node (ref "C22") (pin "2") (pinfunction "2_2") (pintype "passive"))
      (node (ref "C23") (pin "2") (pinfunction "2_2") (pintype "passive"))
      (node (ref "C24") (pin "2") (pinfunction "2_2") (pintype "passive"))
      (node (ref "C25") (pin "2") (pinfunction "2_2") (pintype "passive"))
      (node (ref "C26") (pin "2") (pinfunction "2_2") (pintype "passive"))
      (node (ref "C27") (pin "2") (pinfunction "2_2") (pintype "passive"))
      (node (ref "D0") (pin "C") (pinfunction "A_C") (pintype "passive"))
      (node (ref "D1") (pin "C") (pinfunction "A_C") (pintype "passive"))
      (node (ref "D10") (pin "2") (pinfunction "2_2") (pintype "passive"))
      (node (ref "D11") (pin "2") (pinfunction "2_2") (pintype "passive"))
      (node (ref "D12") (pin "2") (pinfunction "2_2") (pintype "passive"))
      (node (ref "D13") (pin "2") (pinfunction "2_2") (pintype "passive"))
      (node (ref "D14") (pin "2") (pinfunction "2_2") (pintype "passive"))
      (node (ref "D16") (pin "2") (pinfunction "2_2") (pintype "passive"))
      (node (ref "D17") (pin "2") (pinfunction "2_2") (pintype "passive"))
      (node (ref "D18") (pin "2") (pinfunction "2_2") (pintype "passive"))
      (node (ref "D2") (pin "C") (pinfunction "A_C") (pintype "passive"))
      (node (ref "D3") (pin "C") (pinfunction "A_C") (pintype "passive"))
      (node (ref "D4") (pin "C") (pinfunction "A_C") (pintype "passive"))
      (node (ref "D5") (pin "C") (pinfunction "A_C") (pintype "passive"))
      (node (ref "D6") (pin "C") (pinfunction "A_C") (pintype "passive"))
      (node (ref "D7") (pin "2") (pinfunction "2_2") (pintype "passive"))
      (node (ref "D8") (pin "2") (pinfunction "2_2") (pintype "passive"))
      (node (ref "D9") (pin "2") (pinfunction "2_2") (pintype "passive"))
      (node (ref "J1") (pin "3") (pinfunction "GND_3") (pintype "passive"))
      (node (ref "J1") (pin "S1") (pinfunction "Shield_S1") (pintype "passive"))
      (node (ref "J1") (pin "S2") (pinfunction "Shield_S2") (pintype "passive"))
      (node (ref "J10") (pin "0") (pinfunction "0_0") (pintype "passive"))
      (node (ref "J2") (pin "3") (pinfunction "GND_3") (pintype "passive"))
      (node (ref "J2") (pin "S1") (pinfunction "Shield_S1") (pintype "passive"))
      (node (ref "J2") (pin "S2") (pinfunction "Shield_S2") (pintype "passive"))
      (node (ref "J3") (pin "3") (pinfunction "GND_3") (pintype "passive"))
      (node (ref "J3") (pin "S1") (pinfunction "Shield_S1") (pintype "passive"))
      (node (ref "J3") (pin "S2") (pinfunction "Shield_S2") (pintype "passive"))
      (node (ref "J4") (pin "3") (pinfunction "GND_3") (pintype "passive"))
      (node (ref "J4") (pin "S1") (pinfunction "Shield_S1") (pintype "passive"))
      (node (ref "J4") (pin "S2") (pinfunction "Shield_S2") (pintype "passive"))
      (node (ref "J5") (pin "1") (pinfunction "GND_1") (pintype "passive"))
      (node (ref "J6") (pin "1") (pinfunction "GND_1") (pintype "passive"))
      (node (ref "J9") (pin "2") (pinfunction "2_2") (pintype "passive"))
      (node (ref "J9") (pin "S1") (pinfunction "SHIELD1_S1") (pintype "passive"))
      (node (ref "J9") (pin "S2") (pinfunction "SHIELD2_S2") (pintype "passive"))
      (node (ref "U1") (pin "1") (pinfunction "GND_1") (pintype "power_in"))
      (node (ref "U1") (pin "7") (pinfunction "ISEN_7") (pintype "power_in"))
      (node (ref "U1") (pin "9") (pinfunction "PAD_9") (pintype "power_in"))
      (node (ref "U10") (pin "1") (pinfunction "GND_1") (pintype "power_in"))
      (node (ref "U10") (pin "7") (pinfunction "ISEN_7") (pintype "power_in"))
      (node (ref "U10") (pin "9") (pinfunction "PAD_9") (pintype "power_in"))
      (node (ref "U11") (pin "1") (pinfunction "GND_1") (pintype "power_in"))
      (node (ref "U11") (pin "7") (pinfunction "ISEN_7") (pintype "power_in"))
      (node (ref "U11") (pin "9") (pinfunction "PAD_9") (pintype "power_in"))
      (node (ref "U2") (pin "2") (pinfunction "GND_2") (pintype "passive"))
      (node (ref "U2") (pin "6") (pinfunction "PS1_6") (pintype "passive"))
      (node (ref "U2") (pin "7") (pinfunction "PS0_7") (pintype "passive"))
      (node (ref "U3") (pin "0") (pinfunction "GND_0") (pintype "passive"))
      (node (ref "U3") (pin "25") (pinfunction "GND_25") (pintype "passive"))
      (node (ref "U5") (pin "2") (pinfunction "GND_2") (pintype "passive"))
      (node (ref "U6") (pin "1") (pinfunction "GND_1") (pintype "power_in"))
      (node (ref "U6") (pin "7") (pinfunction "ISEN_7") (pintype "power_in"))
      (node (ref "U6") (pin "9") (pinfunction "PAD_9") (pintype "power_in"))
      (node (ref "U7") (pin "11") (pinfunction "GND_11") (pintype "power_in"))
      (node (ref "U8") (pin "7") (pinfunction "GND_7") (pintype "passive"))
    )
    (net (code "42") (name "Net-(D16-Pad1)") (class "Default")
      (node (ref "D16") (pin "1") (pinfunction "1_1") (pintype "passive"))
      (node (ref "R28") (pin "2") (pinfunction "2_2") (pintype "passive"))
    )
    (net (code "43") (name "Net-(D17-Pad1)") (class "Default")
      (node (ref "D17") (pin "1") (pinfunction "1_1") (pintype "passive"))
      (node (ref "R29") (pin "2") (pinfunction "2_2") (pintype "passive"))
    )
    (net (code "44") (name "Net-(D18-Pad1)") (class "Default")
      (node (ref "D18") (pin "1") (pinfunction "1_1") (pintype "passive"))
      (node (ref "R30") (pin "2") (pinfunction "2_2") (pintype "passive"))
    )
    (net (code "45") (name "Net-(F2-Pad2)") (class "Default")
      (node (ref "F2") (pin "2") (pinfunction "2_2") (pintype "passive"))
      (node (ref "J9") (pin "1") (pinfunction "1_1") (pintype "passive"))
    )
    (net (code "46") (name "Net-(J1-PHASEA)") (class "Default")
      (node (ref "D7") (pin "1") (pinfunction "1_1") (pintype "passive"))
      (node (ref "J1") (pin "5") (pinfunction "PHASEA_5") (pintype "passive"))
      (node (ref "U7") (pin "20") (pinfunction "B1_20") (pintype "bidirectional"))
    )
    (net (code "47") (name "Net-(J1-PHASEB)") (class "Default")
      (node (ref "D8") (pin "1") (pinfunction "1_1") (pintype "passive"))
      (node (ref "J1") (pin "6") (pinfunction "PHASEB_6") (pintype "passive"))
      (node (ref "U7") (pin "18") (pinfunction "B2_18") (pintype "bidirectional"))
    )
    (net (code "48") (name "Net-(J2-PHASEA)") (class "Default")
      (node (ref "D9") (pin "1") (pinfunction "1_1") (pintype "passive"))
      (node (ref "J2") (pin "5") (pinfunction "PHASEA_5") (pintype "passive"))
      (node (ref "U7") (pin "17") (pinfunction "B3_17") (pintype "bidirectional"))
    )
    (net (code "49") (name "Net-(J2-PHASEB)") (class "Default")
      (node (ref "D10") (pin "1") (pinfunction "1_1") (pintype "passive"))
      (node (ref "J2") (pin "6") (pinfunction "PHASEB_6") (pintype "passive"))
      (node (ref "U7") (pin "16") (pinfunction "B4_16") (pintype "bidirectional"))
    )
    (net (code "50") (name "Net-(J3-PHASEA)") (class "Default")
      (node (ref "D11") (pin "1") (pinfunction "1_1") (pintype "passive"))
      (node (ref "J3") (pin "5") (pinfunction "PHASEA_5") (pintype "passive"))
      (node (ref "U7") (pin "15") (pinfunction "B5_15") (pintype "bidirectional"))
    )
    (net (code "51") (name "Net-(J3-PHASEB)") (class "Default")
      (node (ref "D12") (pin "1") (pinfunction "1_1") (pintype "passive"))
      (node (ref "J3") (pin "6") (pinfunction "PHASEB_6") (pintype "passive"))
      (node (ref "U7") (pin "14") (pinfunction "B6_14") (pintype "bidirectional"))
    )
    (net (code "52") (name "Net-(J4-PHASEA)") (class "Default")
      (node (ref "D13") (pin "1") (pinfunction "1_1") (pintype "passive"))
      (node (ref "J4") (pin "5") (pinfunction "PHASEA_5") (pintype "passive"))
      (node (ref "U7") (pin "13") (pinfunction "B7_13") (pintype "bidirectional"))
    )
    (net (code "53") (name "Net-(J4-PHASEB)") (class "Default")
      (node (ref "D14") (pin "1") (pinfunction "1_1") (pintype "passive"))
      (node (ref "J4") (pin "6") (pinfunction "PHASEB_6") (pintype "passive"))
      (node (ref "U7") (pin "12") (pinfunction "B8_12") (pintype "bidirectional"))
    )
    (net (code "54") (name "Net-(J5-CTRL)") (class "Default")
      (node (ref "J5") (pin "3") (pinfunction "CTRL_3") (pintype "passive"))
      (node (ref "U8") (pin "13") (pinfunction "B1_13") (pintype "passive"))
    )
    (net (code "55") (name "Net-(J6-CTRL)") (class "Default")
      (node (ref "J6") (pin "3") (pinfunction "CTRL_3") (pintype "passive"))
      (node (ref "U8") (pin "12") (pinfunction "B2_12") (pintype "passive"))
    )
    (net (code "56") (name "Net-(Q3-S)") (class "Default")
      (node (ref "J10") (pin "2") (pinfunction "2_2") (pintype "passive"))
      (node (ref "Q3") (pin "2") (pinfunction "S_2") (pintype "passive"))
    )
    (net (code "57") (name "Net-(U3-3V3_(250mA_MAX))") (class "Default")
      (node (ref "F1") (pin "1") (pinfunction "1_1") (pintype "passive"))
      (node (ref "U3") (pin "26") (pinfunction "3V3_(250mA_MAX)_26") (pintype "passive"))
    )
    (net (code "58") (name "Net-(U3-VIN_(3.6_to_5.5_V))") (class "Default")
      (node (ref "C21") (pin "1") (pinfunction "1_1") (pintype "passive"))
      (node (ref "J8") (pin "2") (pinfunction "2_2") (pintype "passive"))
      (node (ref "U3") (pin "24") (pinfunction "VIN_(3.6_to_5.5_V)_24") (pintype "passive"))
    )
    (net (code "59") (name "Net-(U7-OE)") (class "Default")
      (node (ref "R5") (pin "2") (pinfunction "2_2") (pintype "passive"))
      (node (ref "U7") (pin "10") (pinfunction "OE_10") (pintype "input"))
    )
    (net (code "60") (name "Net-(U8-OE)") (class "Default")
      (node (ref "R6") (pin "1") (pinfunction "1_1") (pintype "passive"))
      (node (ref "U8") (pin "8") (pinfunction "OE_8") (pintype "passive"))
    )
    (net (code "61") (name "unconnected-(U2-3V-Pad1)") (class "Default")
      (node (ref "U2") (pin "1") (pinfunction "3V_1") (pintype "passive+no_connect"))
    )
    (net (code "62") (name "unconnected-(U2-ADR-Pad8)") (class "Default")
      (node (ref "U2") (pin "8") (pinfunction "ADR_8") (pintype "passive+no_connect"))
    )
    (net (code "63") (name "unconnected-(U2-RST-Pad5)") (class "Default")
      (node (ref "U2") (pin "5") (pinfunction "RST_5") (pintype "passive+no_connect"))
    )
    (net (code "64") (name "unconnected-(U3-3V3-Pad14)") (class "Default")
      (node (ref "U3") (pin "14") (pinfunction "3V3_14") (pintype "passive"))
    )
    (net (code "65") (name "unconnected-(U3-D0-Pad1)") (class "Default")
      (node (ref "U3") (pin "1") (pinfunction "D0_1") (pintype "passive"))
    )
    (net (code "66") (name "unconnected-(U3-D1-Pad2)") (class "Default")
      (node (ref "U3") (pin "2") (pinfunction "D1_2") (pintype "passive"))
    )
    (net (code "67") (name "unconnected-(U3-D5-Pad6)") (class "Default")
      (node (ref "U3") (pin "6") (pinfunction "D5_6") (pintype "passive"))
    )
    (net (code "68") (name "unconnected-(U3-D9-Pad10)") (class "Default")
      (node (ref "U3") (pin "10") (pinfunction "D9_10") (pintype "passive"))
    )
    (net (code "69") (name "unconnected-(U3-D11-Pad12)") (class "Default")
      (node (ref "U3") (pin "12") (pinfunction "D11_12") (pintype "passive"))
    )
    (net (code "70") (name "unconnected-(U3-D12-Pad13)") (class "Default")
      (node (ref "U3") (pin "13") (pinfunction "D12_13") (pintype "passive"))
    )
    (net (code "71") (name "unconnected-(U3-D13-Pad37)") (class "Default")
      (node (ref "U3") (pin "37") (pinfunction "D13_37") (pintype "passive"))
    )
    (net (code "72") (name "unconnected-(U3-D22-Pad28)") (class "Default")
      (node (ref "U3") (pin "28") (pinfunction "D22_28") (pintype "passive"))
    )
    (net (code "73") (name "unconnected-(U3-D23-Pad27)") (class "Default")
      (node (ref "U3") (pin "27") (pinfunction "D23_27") (pintype "passive"))
    )
    (net (code "74") (name "unconnected-(U3-D28-Pad19)") (class "Default")
      (node (ref "U3") (pin "19") (pinfunction "D28_19") (pintype "passive"))
    )
    (net (code "75") (name "unconnected-(U3-D29-Pad20)") (class "Default")
      (node (ref "U3") (pin "20") (pinfunction "D29_20") (pintype "passive"))
    )
    (net (code "76") (name "unconnected-(U3-D35-Pad45)") (class "Default")
      (node (ref "U3") (pin "45") (pinfunction "D35_45") (pintype "passive"))
    )
    (net (code "77") (name "unconnected-(U3-D38-Pad42)") (class "Default")
      (node (ref "U3") (pin "42") (pinfunction "D38_42") (pintype "passive"))
    )
    (net (code "78") (name "unconnected-(U3-GND-Pad38)") (class "Default")
      (node (ref "U3") (pin "38") (pinfunction "GND_38") (pintype "passive"))
    )
    (net (code "79") (name "unconnected-(U4-3V3-Pad1)") (class "Default")
      (node (ref "U4") (pin "1") (pinfunction "3V3_1") (pintype "passive+no_connect"))
    )
    (net (code "80") (name "unconnected-(U4-3V3-Pad17)") (class "Default")
      (node (ref "U4") (pin "17") (pinfunction "3V3_17") (pintype "passive+no_connect"))
    )
    (net (code "81") (name "unconnected-(U4-5V-Pad2)") (class "Default")
      (node (ref "U4") (pin "2") (pinfunction "5V_2") (pintype "passive+no_connect"))
    )
    (net (code "82") (name "unconnected-(U4-5V-Pad4)") (class "Default")
      (node (ref "U4") (pin "4") (pinfunction "5V_4") (pintype "passive+no_connect"))
    )
    (net (code "83") (name "unconnected-(U4-GND-Pad6)") (class "Default")
      (node (ref "U4") (pin "6") (pinfunction "GND_6") (pintype "passive+no_connect"))
    )
    (net (code "84") (name "unconnected-(U4-GND-Pad9)") (class "Default")
      (node (ref "U4") (pin "9") (pinfunction "GND_9") (pintype "passive+no_connect"))
    )
    (net (code "85") (name "unconnected-(U4-GND-Pad14)") (class "Default")
      (node (ref "U4") (pin "14") (pinfunction "GND_14") (pintype "passive+no_connect"))
    )
    (net (code "86") (name "unconnected-(U4-GND-Pad20)") (class "Default")
      (node (ref "U4") (pin "20") (pinfunction "GND_20") (pintype "passive+no_connect"))
    )
    (net (code "87") (name "unconnected-(U4-GND-Pad25)") (class "Default")
      (node (ref "U4") (pin "25") (pinfunction "GND_25") (pintype "passive+no_connect"))
    )
    (net (code "88") (name "unconnected-(U4-GND-Pad30)") (class "Default")
      (node (ref "U4") (pin "30") (pinfunction "GND_30") (pintype "passive+no_connect"))
    )
    (net (code "89") (name "unconnected-(U4-GND-Pad34)") (class "Default")
      (node (ref "U4") (pin "34") (pinfunction "GND_34") (pintype "passive"))
    )
    (net (code "90") (name "unconnected-(U4-GND-Pad39)") (class "Default")
      (node (ref "U4") (pin "39") (pinfunction "GND_39") (pintype "passive+no_connect"))
    )
    (net (code "91") (name "unconnected-(U4-GPIO01-Pad29)") (class "Default")
      (node (ref "U4") (pin "29") (pinfunction "GPIO01_29") (pintype "passive+no_connect"))
    )
    (net (code "92") (name "unconnected-(U4-GPIO07-Pad32)") (class "Default")
      (node (ref "U4") (pin "32") (pinfunction "GPIO07_32") (pintype "passive+no_connect"))
    )
    (net (code "93") (name "unconnected-(U4-GPIO9-Pad7)") (class "Default")
      (node (ref "U4") (pin "7") (pinfunction "GPIO9_7") (pintype "passive+no_connect"))
    )
    (net (code "94") (name "unconnected-(U4-GPIO11-Pad31)") (class "Default")
      (node (ref "U4") (pin "31") (pinfunction "GPIO11_31") (pintype "passive+no_connect"))
    )
    (net (code "95") (name "unconnected-(U4-GPIO12-Pad15)") (class "Default")
      (node (ref "U4") (pin "15") (pinfunction "GPIO12_15") (pintype "passive+no_connect"))
    )
    (net (code "96") (name "unconnected-(U4-GPIO13-Pad33)") (class "Default")
      (node (ref "U4") (pin "33") (pinfunction "GPIO13_33") (pintype "passive+no_connect"))
    )
    (net (code "97") (name "unconnected-(U4-I2S0_FS-Pad35)") (class "Default")
      (node (ref "U4") (pin "35") (pinfunction "I2S0_FS_35") (pintype "passive+no_connect"))
    )
    (net (code "98") (name "unconnected-(U4-I2S0_SCK-Pad12)") (class "Default")
      (node (ref "U4") (pin "12") (pinfunction "I2S0_SCK_12") (pintype "passive+no_connect"))
    )
    (net (code "99") (name "unconnected-(U4-I2S0_SDIN-Pad38)") (class "Default")
      (node (ref "U4") (pin "38") (pinfunction "I2S0_SDIN_38") (pintype "passive+no_connect"))
    )
    (net (code "100") (name "unconnected-(U4-I2S0_SDOUT-Pad40)") (class "Default")
      (node (ref "U4") (pin "40") (pinfunction "I2S0_SDOUT_40") (pintype "passive+no_connect"))
    )
    (net (code "101") (name "unconnected-(U4-SPI0_CS0-Pad24)") (class "Default")
      (node (ref "U4") (pin "24") (pinfunction "SPI0_CS0_24") (pintype "passive+no_connect"))
    )
    (net (code "102") (name "unconnected-(U4-SPI0_CS1-Pad26)") (class "Default")
      (node (ref "U4") (pin "26") (pinfunction "SPI0_CS1_26") (pintype "passive+no_connect"))
    )
    (net (code "103") (name "unconnected-(U4-SPI0_MISO-Pad21)") (class "Default")
      (node (ref "U4") (pin "21") (pinfunction "SPI0_MISO_21") (pintype "passive+no_connect"))
    )
    (net (code "104") (name "unconnected-(U4-SPI0_MOSI-Pad19)") (class "Default")
      (node (ref "U4") (pin "19") (pinfunction "SPI0_MOSI_19") (pintype "passive+no_connect"))
    )
    (net (code "105") (name "unconnected-(U4-SPI0_SCK-Pad23)") (class "Default")
      (node (ref "U4") (pin "23") (pinfunction "SPI0_SCK_23") (pintype "passive+no_connect"))
    )
    (net (code "106") (name "unconnected-(U4-SPI1_CS0-Pad18)") (class "Default")
      (node (ref "U4") (pin "18") (pinfunction "SPI1_CS0_18") (pintype "passive+no_connect"))
    )
    (net (code "107") (name "unconnected-(U4-SPI1_CS1-Pad16)") (class "Default")
      (node (ref "U4") (pin "16") (pinfunction "SPI1_CS1_16") (pintype "passive+no_connect"))
    )
    (net (code "108") (name "unconnected-(U4-SPI1_MISO-Pad22)") (class "Default")
      (node (ref "U4") (pin "22") (pinfunction "SPI1_MISO_22") (pintype "passive+no_connect"))
    )
    (net (code "109") (name "unconnected-(U4-SPI1_MOSI-Pad37)") (class "Default")
      (node (ref "U4") (pin "37") (pinfunction "SPI1_MOSI_37") (pintype "passive+no_connect"))
    )
    (net (code "110") (name "unconnected-(U4-SPI1_SCK-Pad13)") (class "Default")
      (node (ref "U4") (pin "13") (pinfunction "SPI1_SCK_13") (pintype "passive+no_connect"))
    )
    (net (code "111") (name "unconnected-(U5-3Vo-Pad1)") (class "Default")
      (node (ref "U5") (pin "1") (pinfunction "3Vo_1") (pintype "passive+no_connect"))
    )
    (net (code "112") (name "unconnected-(U5-DRDY-Pad5)") (class "Default")
      (node (ref "U5") (pin "5") (pinfunction "DRDY_5") (pintype "passive+no_connect"))
    )
    (net (code "113") (name "unconnected-(U8-A3-Pad4)") (class "Default")
      (node (ref "U8") (pin "4") (pinfunction "A3_4") (pintype "passive+no_connect"))
    )
    (net (code "114") (name "unconnected-(U8-A4-Pad5)") (class "Default")
      (node (ref "U8") (pin "5") (pinfunction "A4_5") (pintype "passive+no_connect"))
    )
    (net (code "115") (name "unconnected-(U8-B3-Pad11)") (class "Default")
      (node (ref "U8") (pin "11") (pinfunction "B3_11") (pintype "passive+no_connect"))
    )
    (net (code "116") (name "unconnected-(U8-B4-Pad10)") (class "Default")
      (node (ref "U8") (pin "10") (pinfunction "B4_10") (pintype "passive+no_connect"))
    )
  )
)
